# ESP_Home_Automation.net
KiCad netlist of a schematic drawn in EasyEDA
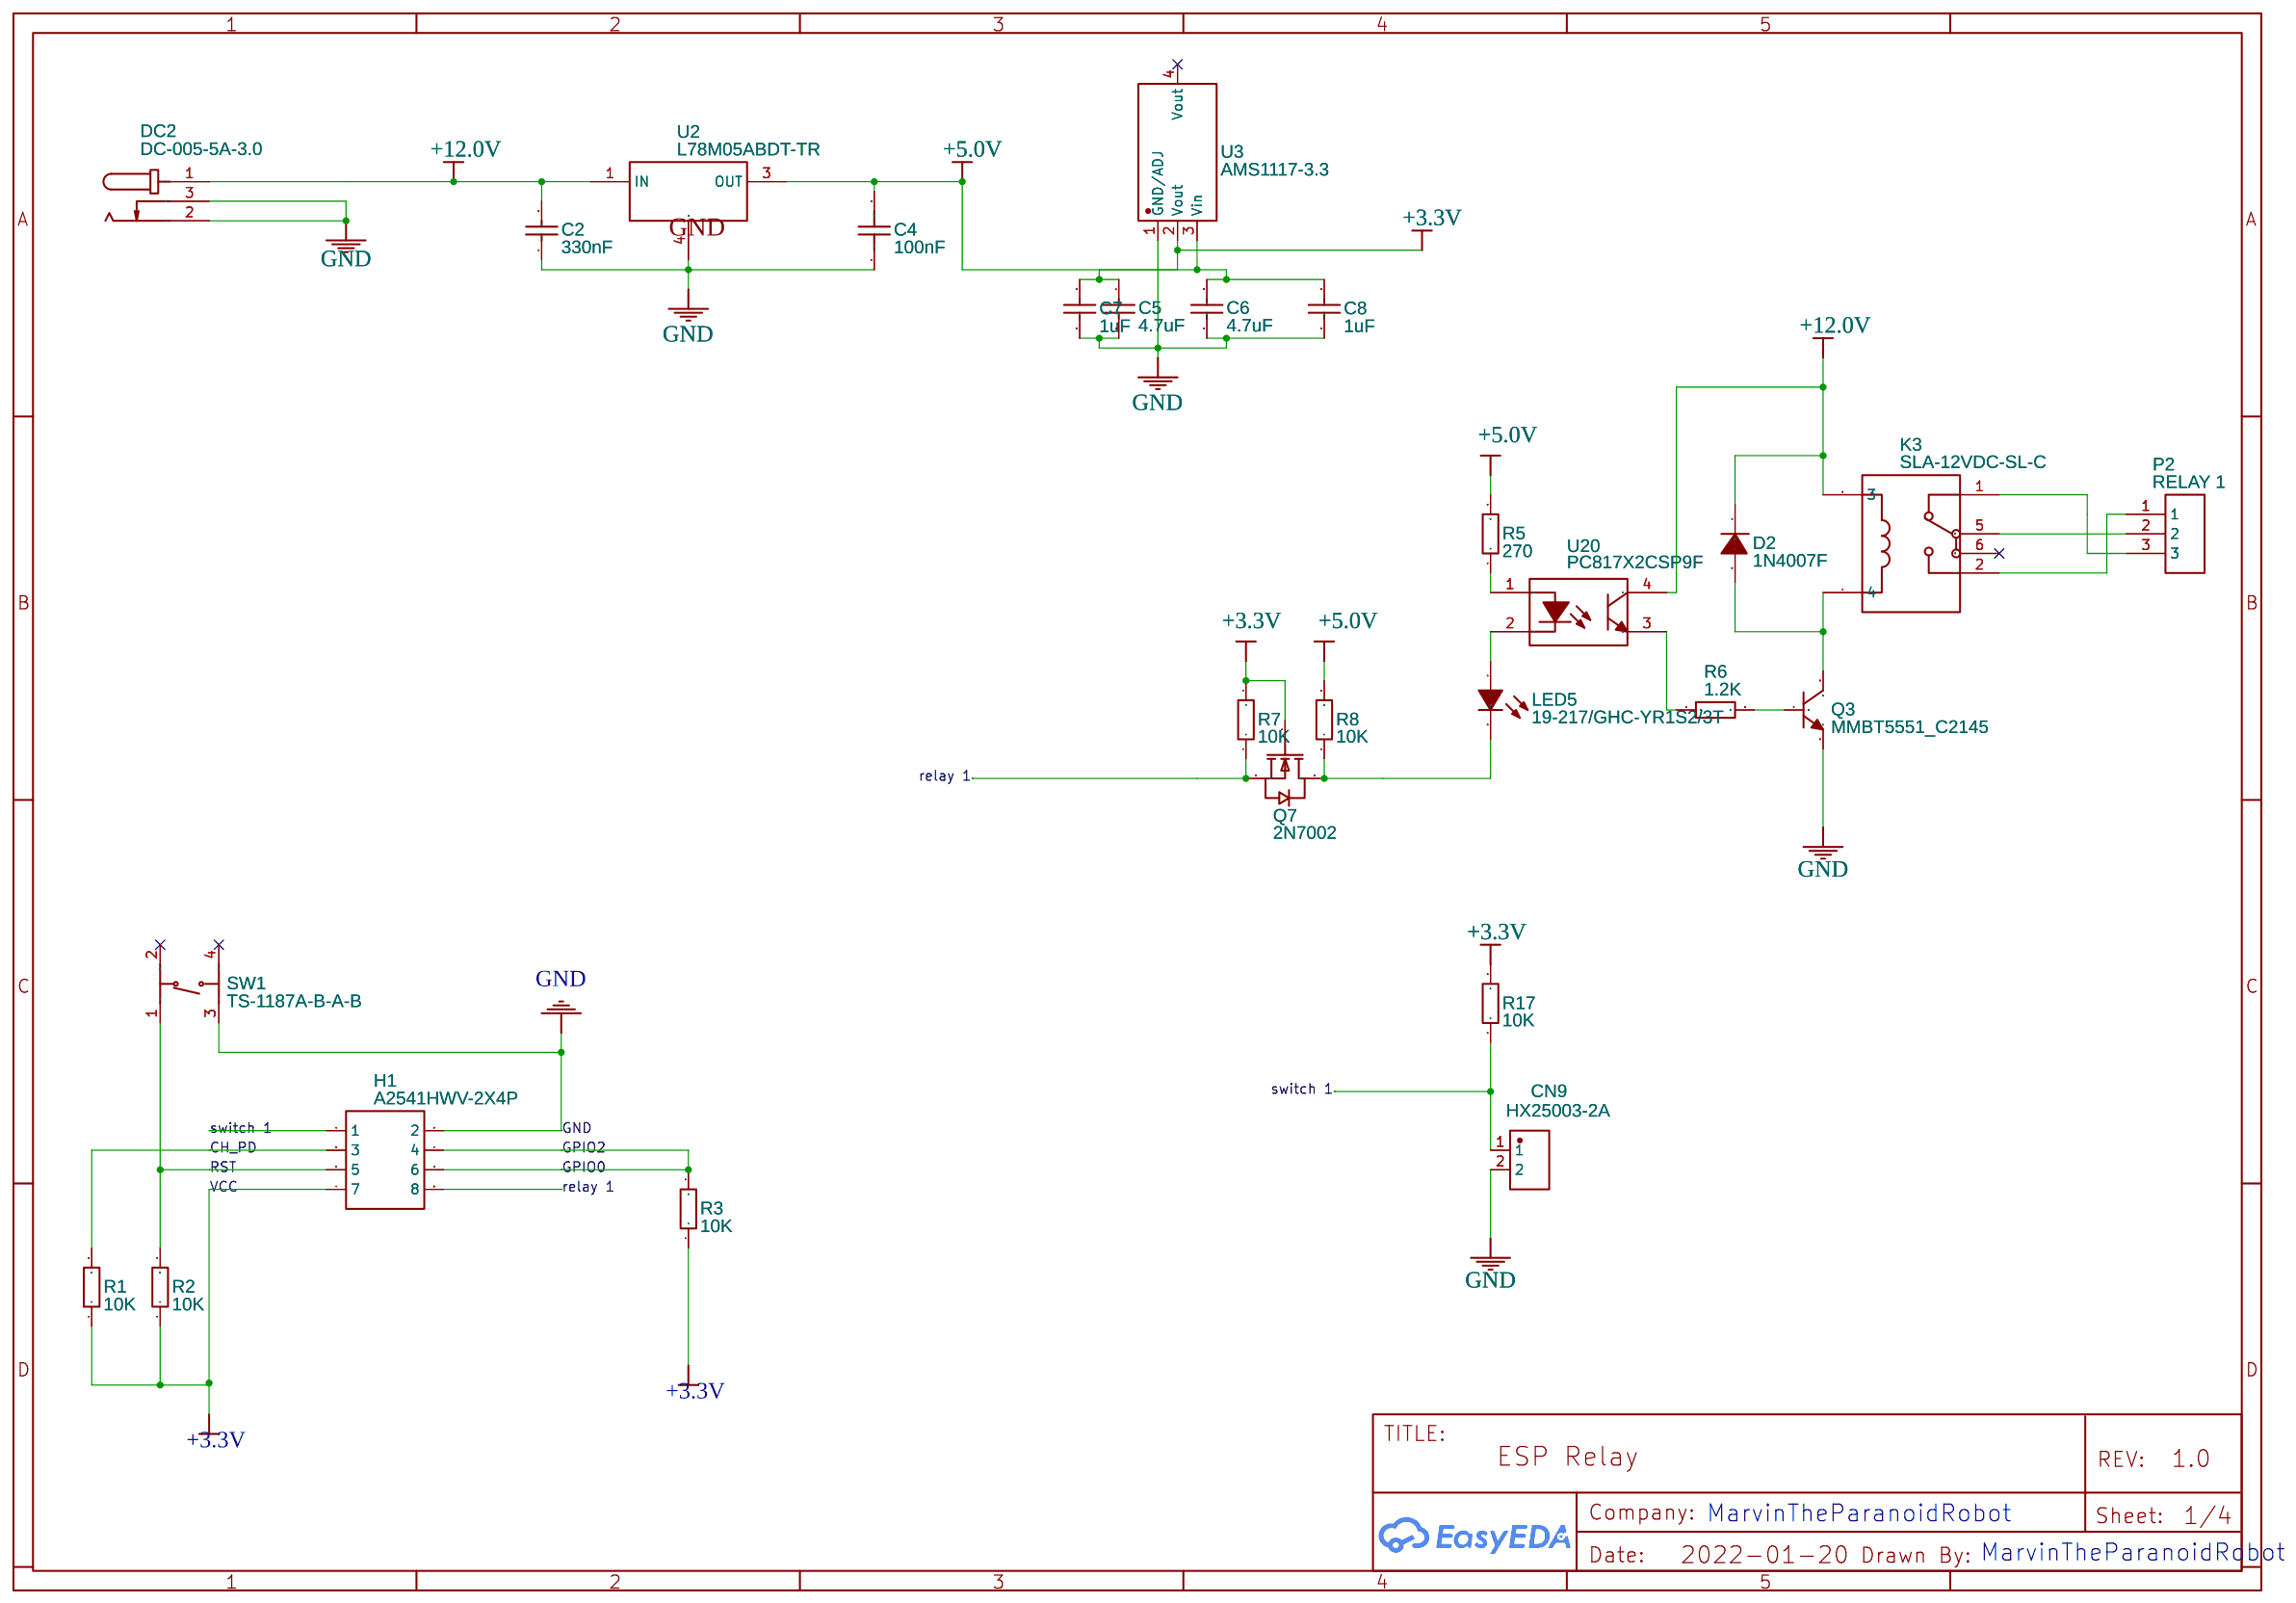
[diagram p0: Sheet_1]
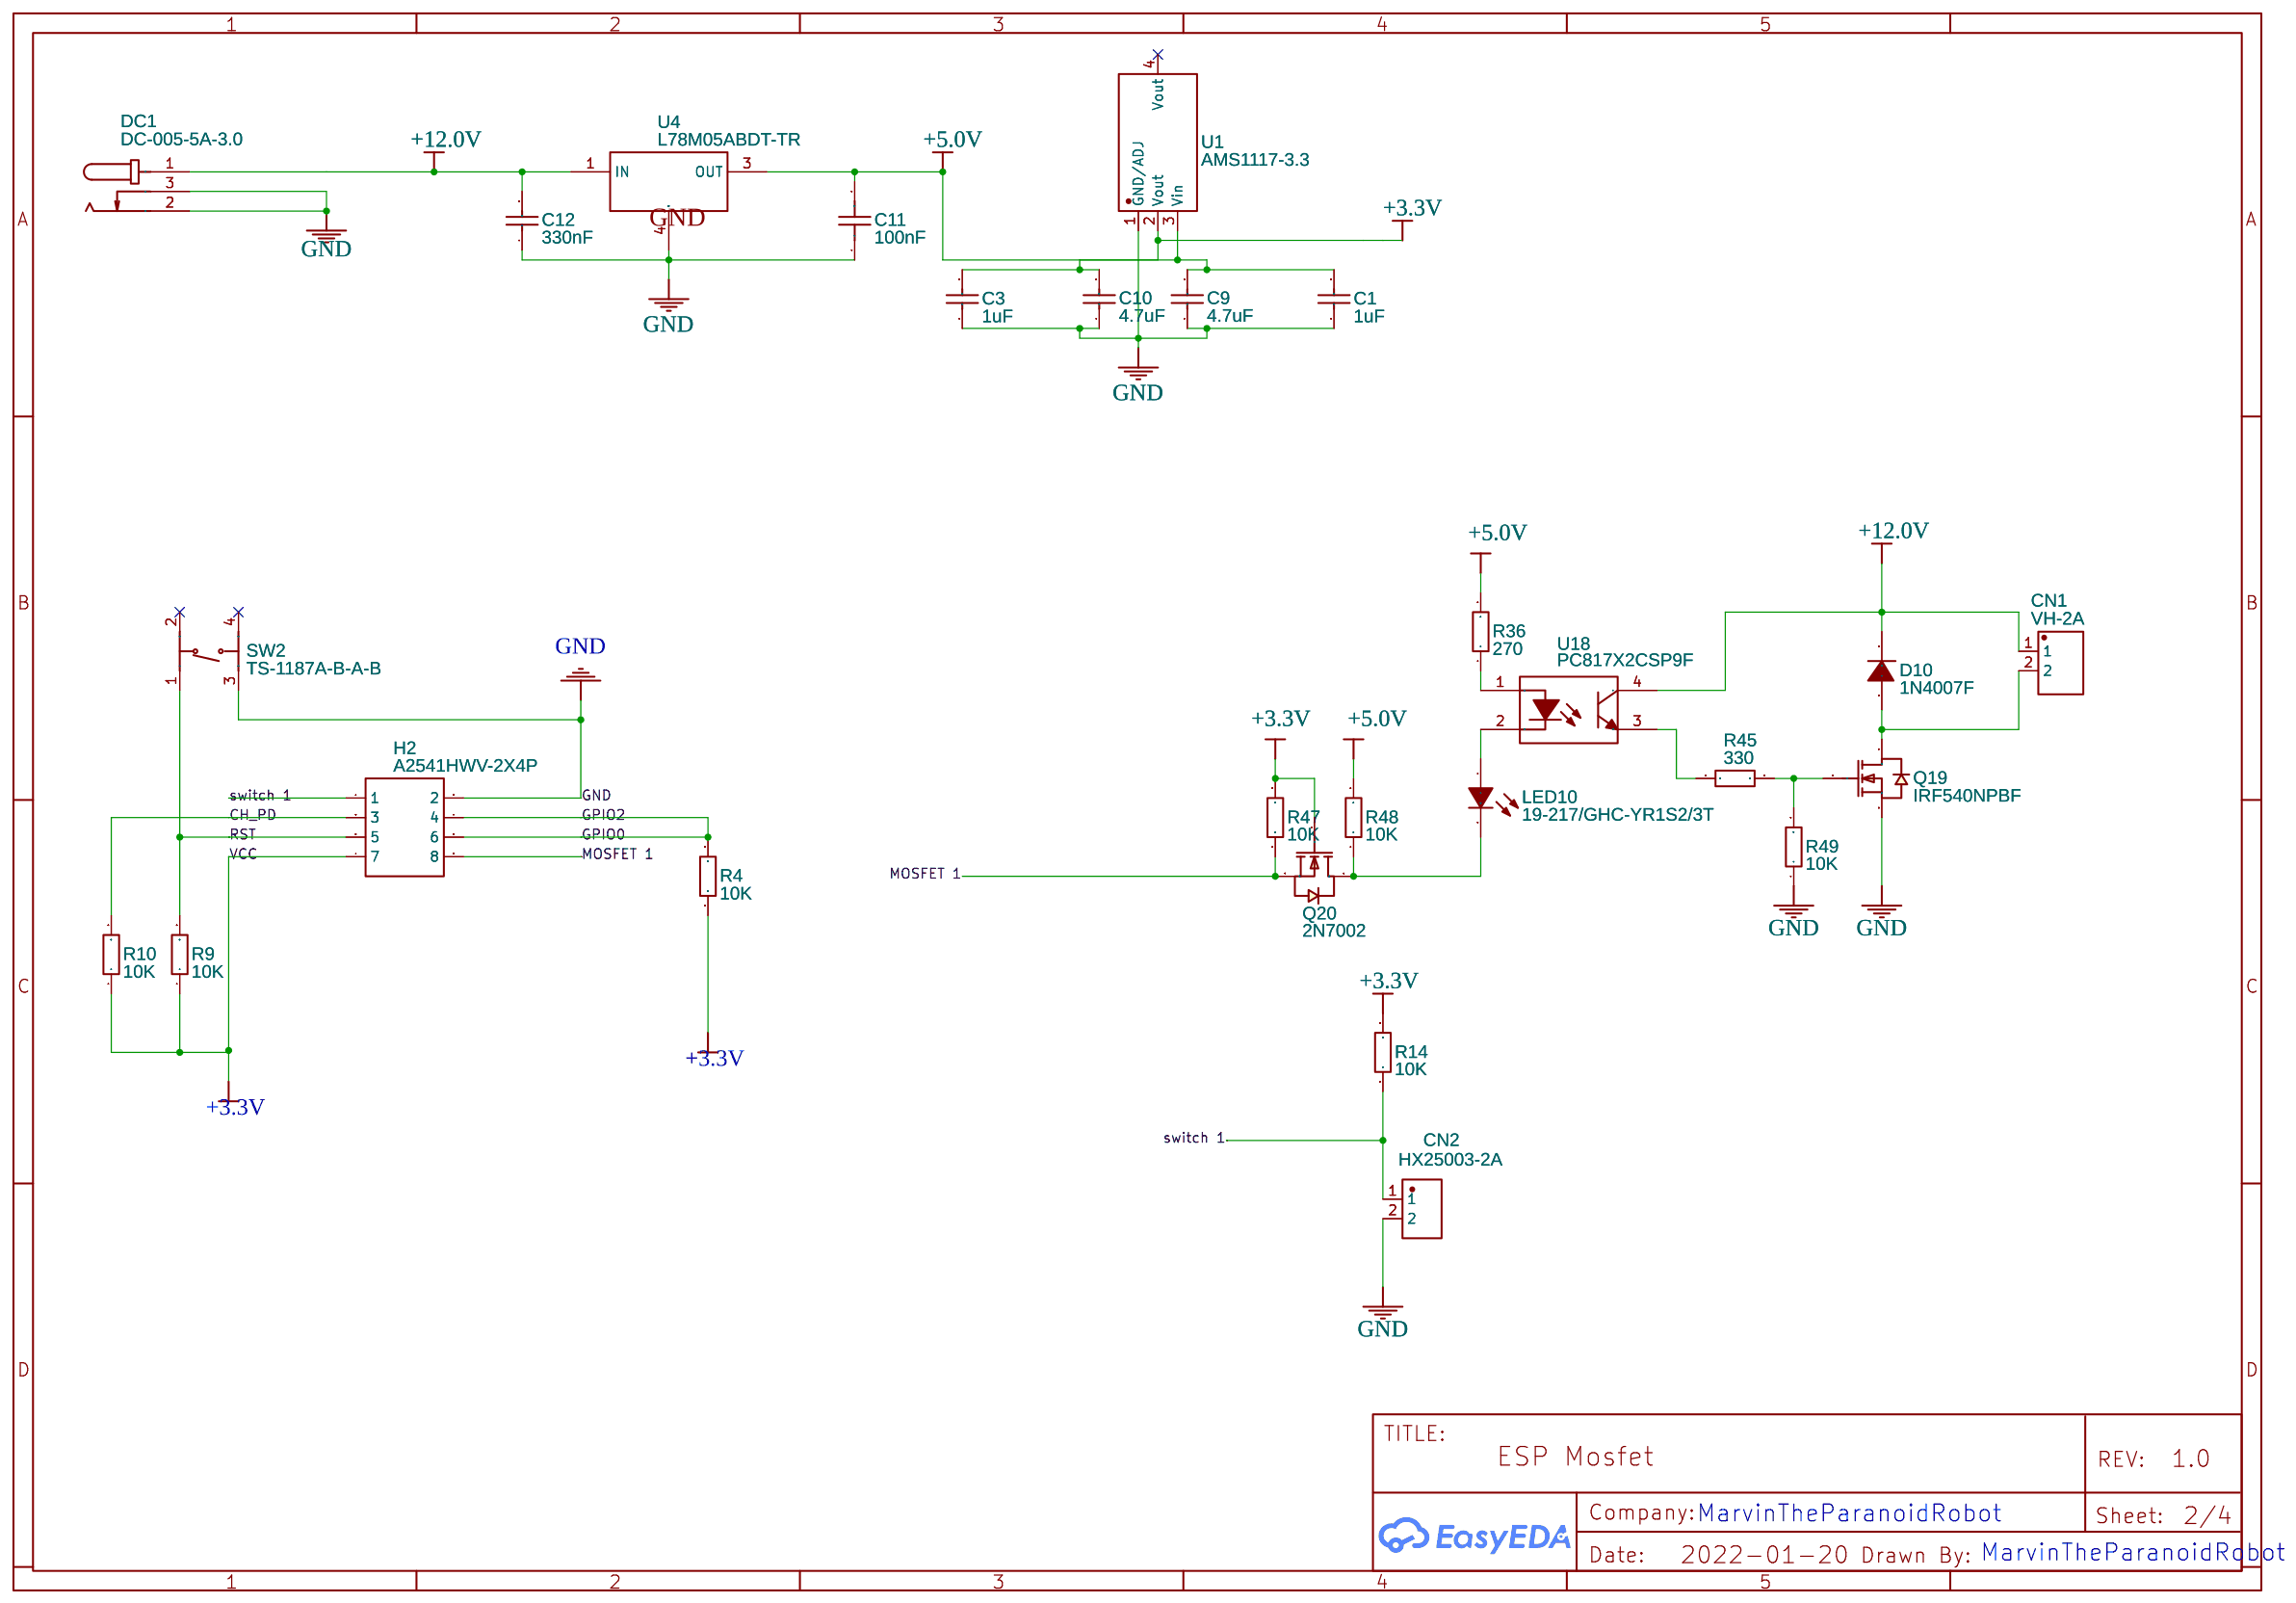
[diagram p1: Sheet_2]
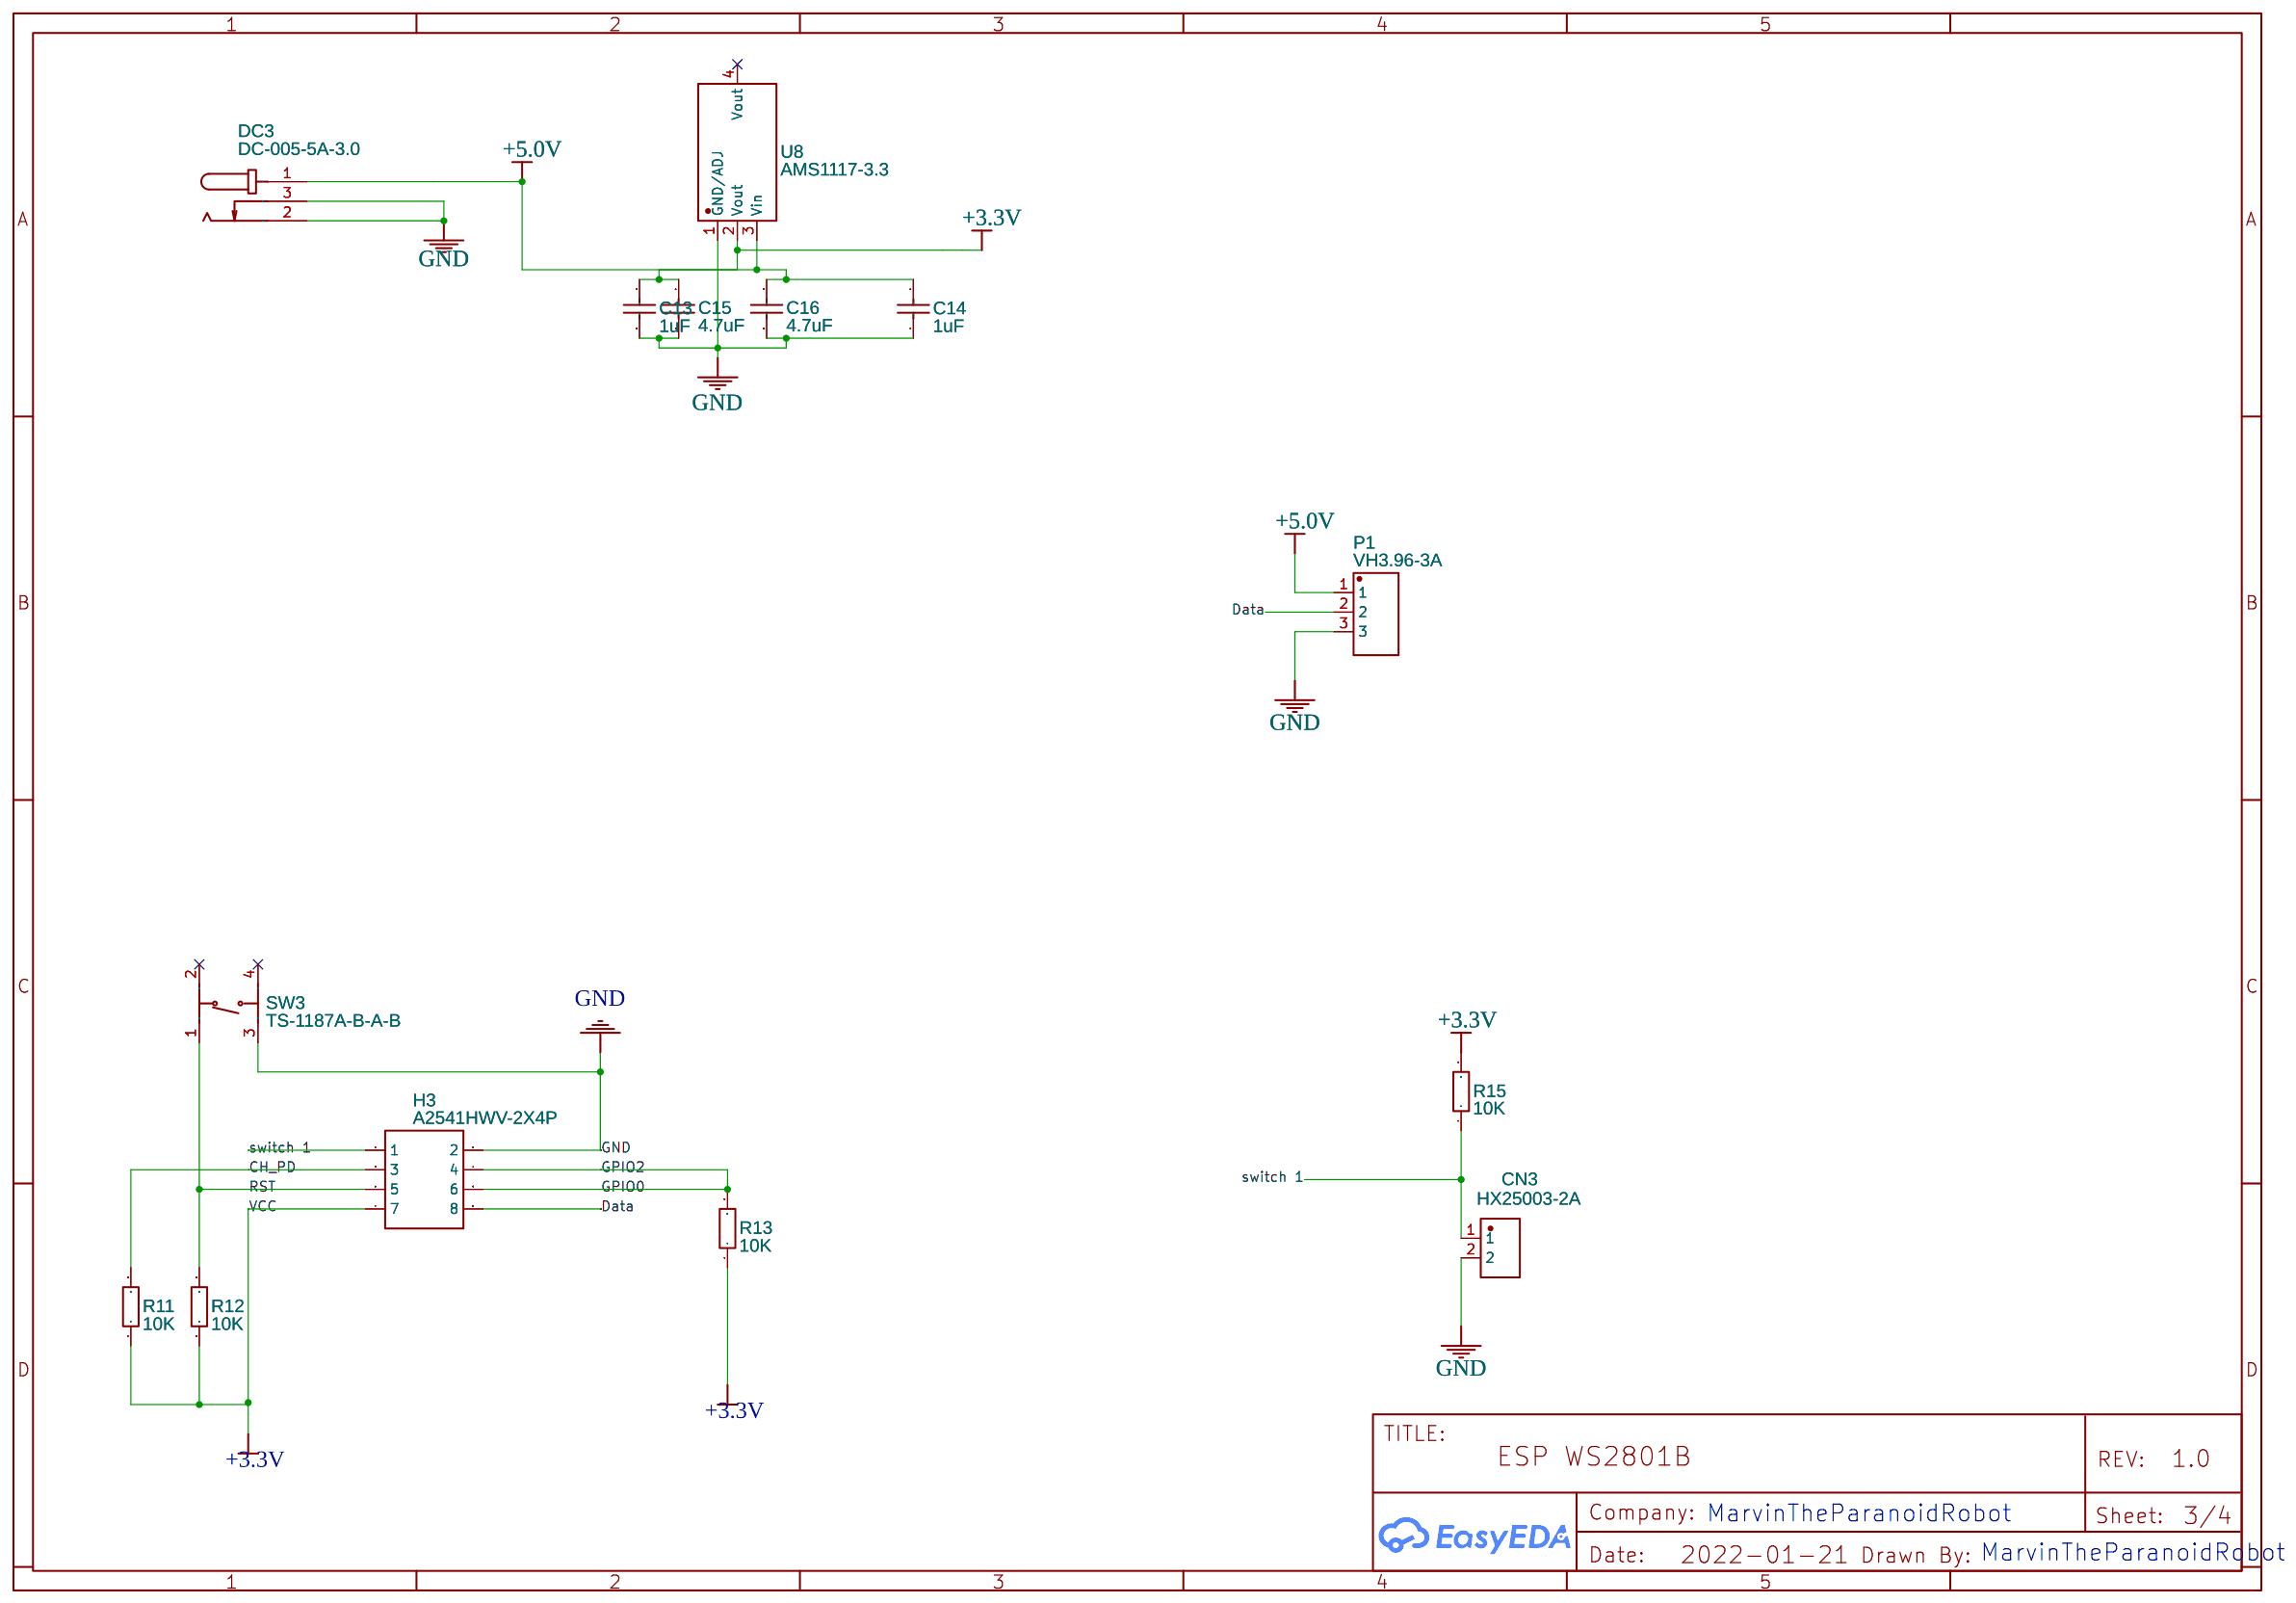
[diagram p2: Sheet_3]
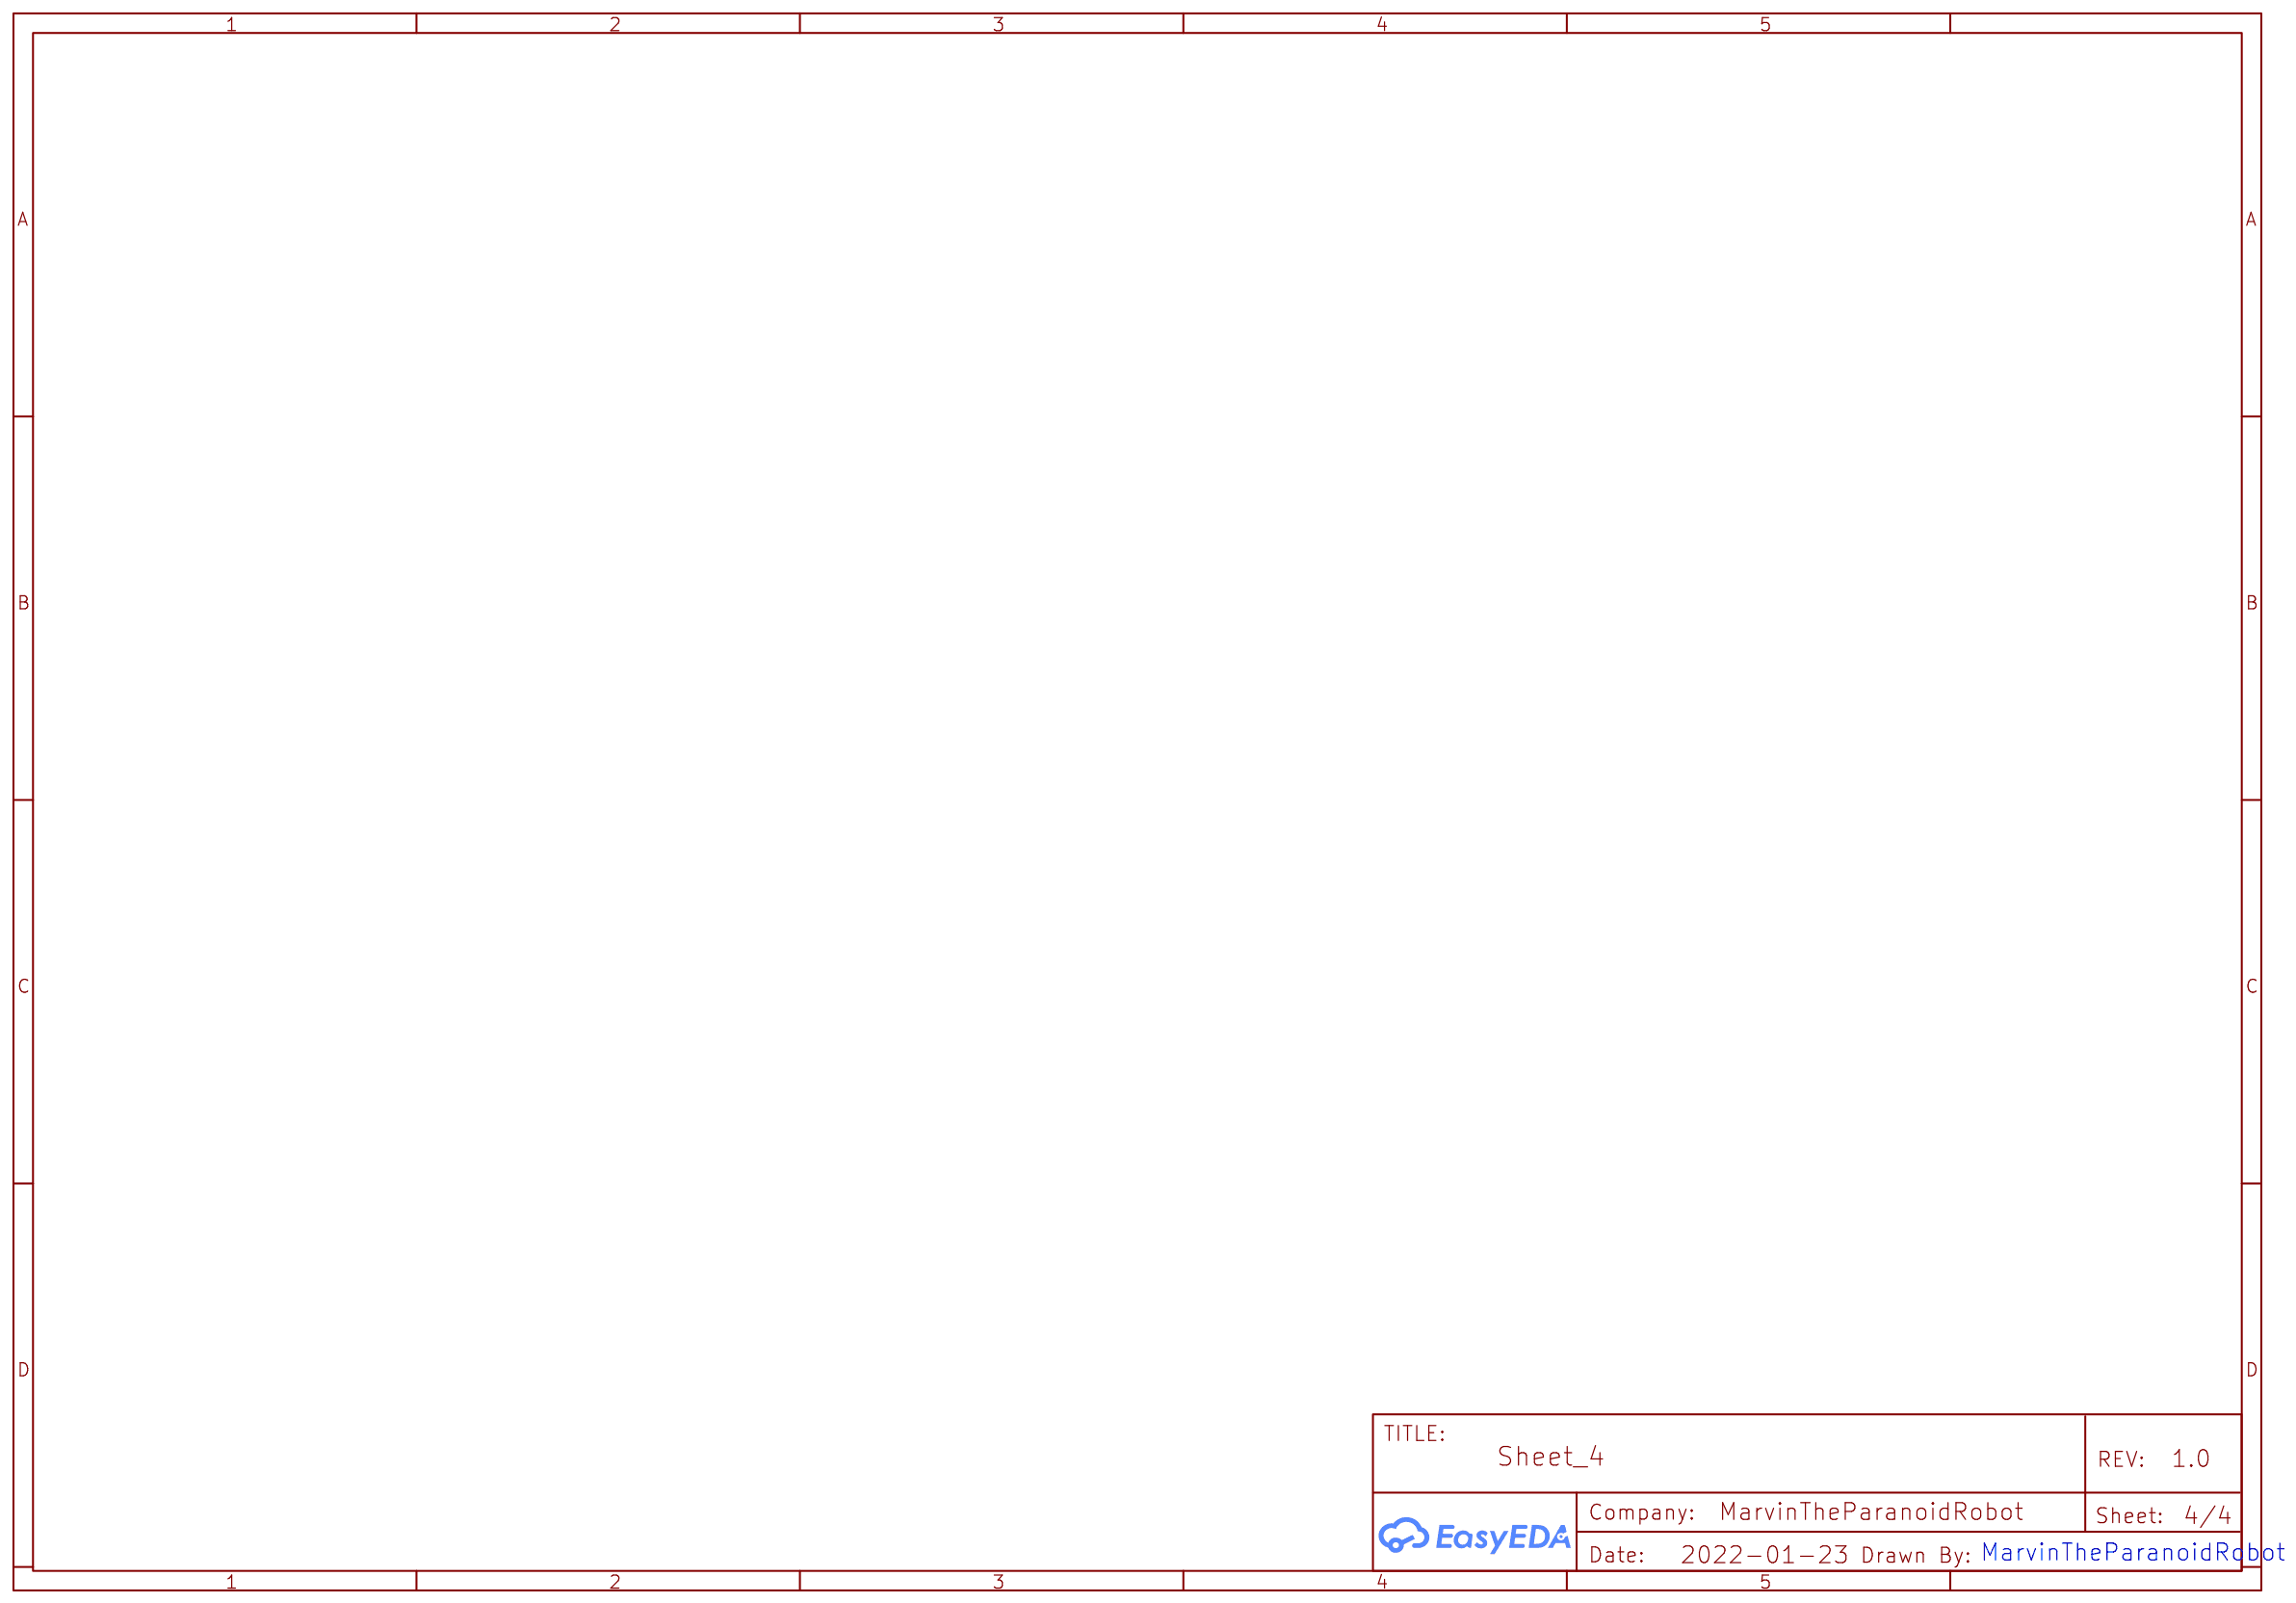
[diagram p3: Sheet_4]

(export (version "E")
  (design (tool "Eeschema 10.0.6"))
  (components
    (comp (ref "C2")
      (value "330nF")
      (fields
        (field (name "BOM_Manufacturer Part") "0805B334K500NT")
        (field (name "BOM_Supplier Part") "C1740")
      )
      (libsource (lib "") (part "0805B334K500NT"))
    )
    (comp (ref "C4")
      (value "100nF")
      (fields
        (field (name "BOM_Manufacturer Part") "CC0603KRX7R9BB104")
        (field (name "BOM_Supplier Part") "C14663")
      )
      (libsource (lib "") (part "CC0603KRX7R9BB104"))
    )
    (comp (ref "C5")
      (value "4.7uF")
      (fields
        (field (name "BOM_Manufacturer Part") "1206B475K500NT")
        (field (name "BOM_Supplier Part") "C29823")
      )
      (libsource (lib "") (part "1206B475K500NT"))
    )
    (comp (ref "C6")
      (value "4.7uF")
      (fields
        (field (name "BOM_Manufacturer Part") "1206B475K500NT")
        (field (name "BOM_Supplier Part") "C29823")
      )
      (libsource (lib "") (part "1206B475K500NT"))
    )
    (comp (ref "C7")
      (value "1uF")
      (fields
        (field (name "BOM_Manufacturer Part") "CL10A105KB8NNNC")
        (field (name "BOM_Supplier Part") "C15849")
      )
      (libsource (lib "") (part "CL10A105KB8NNNC"))
    )
    (comp (ref "C8")
      (value "1uF")
      (fields
        (field (name "BOM_Manufacturer Part") "CL10A105KB8NNNC")
        (field (name "BOM_Supplier Part") "C15849")
      )
      (libsource (lib "") (part "CL10A105KB8NNNC"))
    )
    (comp (ref "CN9")
      (value "HX25003-2A")
      (fields (field (name "BOM_Supplier Part") "C442299"))
      (libsource (lib "") (part "HX25003-2A"))
    )
    (comp (ref "D2")
      (value "1N4007F")
      (fields (field (name "BOM_Supplier Part") "C110856"))
      (libsource (lib "") (part "1N4007F"))
    )
    (comp (ref "DC2")
      (value "DC-005-5A-3.0")
      (fields (field (name "BOM_Supplier Part") "C388625"))
      (libsource (lib "") (part "DC-005-5A-3.0"))
    )
    (comp (ref "H1")
      (value "A2541HWV-2X4P")
      (fields
        (field (name "BOM_Manufacturer Part") "A2541HWV-2x4P")
        (field (name "BOM_Supplier Part") "C239344")
      )
      (libsource (lib "") (part "A2541HWV-2X4P"))
    )
    (comp (ref "K3")
      (value "SLA-12VDC-SL-C")
      (fields (field (name "BOM_Supplier Part") "C125736"))
      (libsource (lib "") (part "SLA-12VDC-SL-C"))
    )
    (comp (ref "LED5")
      (value "19-217/GHC-YR1S2/3T")
      (fields (field (name "BOM_Supplier Part") "C72043"))
      (libsource (lib "") (part "19-217/GHC-YR1S2/3T"))
    )
    (comp (ref "P2")
      (value "RELAY 1")
      (fields
        (field (name "BOM_Manufacturer Part") "WJ128V-5.0-3P")
        (field (name "BOM_Supplier Part") "C8270")
      )
      (libsource (lib "") (part "WJ128V-5.0-3P"))
    )
    (comp (ref "Q3")
      (value "MMBT5551_C2145")
      (fields (field (name "BOM_Manufacturer Part") "MMBT5551") (field (name "BOM_Supplier Part") "C2145"))
      (libsource (lib "") (part "MMBT5551_C2145"))
    )
    (comp (ref "Q7")
      (value "2N7002")
      (fields (field (name "BOM_Supplier Part") "C8545"))
      (libsource (lib "") (part "2N7002"))
    )
    (comp (ref "R1")
      (value "10K")
      (fields
        (field (name "BOM_Manufacturer Part") "1206W4F1002T5E")
        (field (name "BOM_Supplier Part") "C17902")
      )
      (libsource (lib "") (part "1206W4F1002T5E"))
    )
    (comp (ref "R2")
      (value "10K")
      (fields
        (field (name "BOM_Manufacturer Part") "1206W4F1002T5E")
        (field (name "BOM_Supplier Part") "C17902")
      )
      (libsource (lib "") (part "1206W4F1002T5E"))
    )
    (comp (ref "R3")
      (value "10K")
      (fields
        (field (name "BOM_Manufacturer Part") "1206W4F1002T5E")
        (field (name "BOM_Supplier Part") "C17902")
      )
      (libsource (lib "") (part "1206W4F1002T5E"))
    )
    (comp (ref "R5")
      (value "270")
      (fields
        (field (name "BOM_Manufacturer Part") "0603WAF2700T5E")
        (field (name "BOM_Supplier Part") "C22966")
      )
      (libsource (lib "") (part "0603WAF2700T5E"))
    )
    (comp (ref "R6")
      (value "1.2K")
      (fields
        (field (name "BOM_Manufacturer Part") "0805W8F1201T5E")
        (field (name "BOM_Supplier Part") "C17379")
      )
      (libsource (lib "") (part "0805W8F1201T5E"))
    )
    (comp (ref "R7")
      (value "10K")
      (fields
        (field (name "BOM_Manufacturer Part") "1206W4F1002T5E")
        (field (name "BOM_Supplier Part") "C17902")
      )
      (libsource (lib "") (part "1206W4F1002T5E"))
    )
    (comp (ref "R8")
      (value "10K")
      (fields
        (field (name "BOM_Manufacturer Part") "1206W4F1002T5E")
        (field (name "BOM_Supplier Part") "C17902")
      )
      (libsource (lib "") (part "1206W4F1002T5E"))
    )
    (comp (ref "R17")
      (value "10K")
      (fields
        (field (name "BOM_Manufacturer Part") "1206W4F1002T5E")
        (field (name "BOM_Supplier Part") "C17902")
      )
      (libsource (lib "") (part "1206W4F1002T5E"))
    )
    (comp (ref "SW1")
      (value "TS-1187A-B-A-B")
      (fields (field (name "BOM_Supplier Part") "C318884"))
      (libsource (lib "") (part "TS-1187A-B-A-B"))
    )
    (comp (ref "U2")
      (value "L78M05ABDT-TR")
      (fields (field (name "BOM_Supplier Part") "C58069"))
      (libsource (lib "") (part "L78M05ABDT-TR"))
    )
    (comp (ref "U3")
      (value "AMS1117-3.3")
      (fields (field (name "BOM_Supplier Part") "C6186"))
      (libsource (lib "") (part "AMS1117-3.3"))
    )
    (comp (ref "U20")
      (value "PC817X2CSP9F")
      (fields (field (name "BOM_Supplier Part") "C66405"))
      (libsource (lib "") (part "PC817X2CSP9F"))
    )
    (comp (ref "C1")
      (value "1uF")
      (fields
        (field (name "BOM_Manufacturer Part") "CL10A105KB8NNNC")
        (field (name "BOM_Supplier Part") "C15849")
      )
      (libsource (lib "") (part "CL10A105KB8NNNC"))
    )
    (comp (ref "C3")
      (value "1uF")
      (fields
        (field (name "BOM_Manufacturer Part") "CL10A105KB8NNNC")
        (field (name "BOM_Supplier Part") "C15849")
      )
      (libsource (lib "") (part "CL10A105KB8NNNC"))
    )
    (comp (ref "C9")
      (value "4.7uF")
      (fields
        (field (name "BOM_Manufacturer Part") "1206B475K500NT")
        (field (name "BOM_Supplier Part") "C29823")
      )
      (libsource (lib "") (part "1206B475K500NT"))
    )
    (comp (ref "C10")
      (value "4.7uF")
      (fields
        (field (name "BOM_Manufacturer Part") "1206B475K500NT")
        (field (name "BOM_Supplier Part") "C29823")
      )
      (libsource (lib "") (part "1206B475K500NT"))
    )
    (comp (ref "C11")
      (value "100nF")
      (fields
        (field (name "BOM_Manufacturer Part") "CC0603KRX7R9BB104")
        (field (name "BOM_Supplier Part") "C14663")
      )
      (libsource (lib "") (part "CC0603KRX7R9BB104"))
    )
    (comp (ref "C12")
      (value "330nF")
      (fields
        (field (name "BOM_Manufacturer Part") "0805B334K500NT")
        (field (name "BOM_Supplier Part") "C1740")
      )
      (libsource (lib "") (part "0805B334K500NT"))
    )
    (comp (ref "CN1")
      (value "VH-2A")
      (fields (field (name "BOM_Supplier Part") "C16728"))
      (libsource (lib "") (part "VH-2A"))
    )
    (comp (ref "CN2")
      (value "HX25003-2A")
      (fields (field (name "BOM_Supplier Part") "C442299"))
      (libsource (lib "") (part "HX25003-2A"))
    )
    (comp (ref "D10")
      (value "1N4007F")
      (fields (field (name "BOM_Supplier Part") "C110856"))
      (libsource (lib "") (part "1N4007F"))
    )
    (comp (ref "DC1")
      (value "DC-005-5A-3.0")
      (fields (field (name "BOM_Supplier Part") "C388625"))
      (libsource (lib "") (part "DC-005-5A-3.0"))
    )
    (comp (ref "H2")
      (value "A2541HWV-2X4P")
      (fields
        (field (name "BOM_Manufacturer Part") "A2541HWV-2x4P")
        (field (name "BOM_Supplier Part") "C239344")
      )
      (libsource (lib "") (part "A2541HWV-2X4P"))
    )
    (comp (ref "LED10")
      (value "19-217/GHC-YR1S2/3T")
      (fields (field (name "BOM_Supplier Part") "C72043"))
      (libsource (lib "") (part "19-217/GHC-YR1S2/3T"))
    )
    (comp (ref "Q19")
      (value "IRF540NPBF")
      (fields (field (name "BOM_Supplier Part") "C2566"))
      (libsource (lib "") (part "IRF540NPBF"))
    )
    (comp (ref "Q20")
      (value "2N7002")
      (fields (field (name "BOM_Supplier Part") "C8545"))
      (libsource (lib "") (part "2N7002"))
    )
    (comp (ref "R4")
      (value "10K")
      (fields
        (field (name "BOM_Manufacturer Part") "1206W4F1002T5E")
        (field (name "BOM_Supplier Part") "C17902")
      )
      (libsource (lib "") (part "1206W4F1002T5E"))
    )
    (comp (ref "R9")
      (value "10K")
      (fields
        (field (name "BOM_Manufacturer Part") "1206W4F1002T5E")
        (field (name "BOM_Supplier Part") "C17902")
      )
      (libsource (lib "") (part "1206W4F1002T5E"))
    )
    (comp (ref "R10")
      (value "10K")
      (fields
        (field (name "BOM_Manufacturer Part") "1206W4F1002T5E")
        (field (name "BOM_Supplier Part") "C17902")
      )
      (libsource (lib "") (part "1206W4F1002T5E"))
    )
    (comp (ref "R14")
      (value "10K")
      (fields
        (field (name "BOM_Manufacturer Part") "1206W4F1002T5E")
        (field (name "BOM_Supplier Part") "C17902")
      )
      (libsource (lib "") (part "1206W4F1002T5E"))
    )
    (comp (ref "R36")
      (value "270")
      (fields
        (field (name "BOM_Manufacturer Part") "0603WAF2700T5E")
        (field (name "BOM_Supplier Part") "C22966")
      )
      (libsource (lib "") (part "0603WAF2700T5E"))
    )
    (comp (ref "R45")
      (value "330")
      (fields
        (field (name "BOM_Manufacturer Part") "0805W8F3300T5E")
        (field (name "BOM_Supplier Part") "C17630")
      )
      (libsource (lib "") (part "0805W8F3300T5E"))
    )
    (comp (ref "R47")
      (value "10K")
      (fields
        (field (name "BOM_Manufacturer Part") "1206W4F1002T5E")
        (field (name "BOM_Supplier Part") "C17902")
      )
      (libsource (lib "") (part "1206W4F1002T5E"))
    )
    (comp (ref "R48")
      (value "10K")
      (fields
        (field (name "BOM_Manufacturer Part") "1206W4F1002T5E")
        (field (name "BOM_Supplier Part") "C17902")
      )
      (libsource (lib "") (part "1206W4F1002T5E"))
    )
    (comp (ref "R49")
      (value "10K")
      (fields
        (field (name "BOM_Manufacturer Part") "1206W4F1002T5E")
        (field (name "BOM_Supplier Part") "C17902")
      )
      (libsource (lib "") (part "1206W4F1002T5E"))
    )
    (comp (ref "SW2")
      (value "TS-1187A-B-A-B")
      (fields (field (name "BOM_Supplier Part") "C318884"))
      (libsource (lib "") (part "TS-1187A-B-A-B"))
    )
    (comp (ref "U1")
      (value "AMS1117-3.3")
      (fields (field (name "BOM_Supplier Part") "C6186"))
      (libsource (lib "") (part "AMS1117-3.3"))
    )
    (comp (ref "U4")
      (value "L78M05ABDT-TR")
      (fields (field (name "BOM_Supplier Part") "C58069"))
      (libsource (lib "") (part "L78M05ABDT-TR"))
    )
    (comp (ref "U18")
      (value "PC817X2CSP9F")
      (fields (field (name "BOM_Supplier Part") "C66405"))
      (libsource (lib "") (part "PC817X2CSP9F"))
    )
    (comp (ref "C13")
      (value "1uF")
      (fields
        (field (name "BOM_Manufacturer Part") "CL10A105KB8NNNC")
        (field (name "BOM_Supplier Part") "C15849")
      )
      (libsource (lib "") (part "CL10A105KB8NNNC"))
    )
    (comp (ref "C14")
      (value "1uF")
      (fields
        (field (name "BOM_Manufacturer Part") "CL10A105KB8NNNC")
        (field (name "BOM_Supplier Part") "C15849")
      )
      (libsource (lib "") (part "CL10A105KB8NNNC"))
    )
    (comp (ref "C15")
      (value "4.7uF")
      (fields
        (field (name "BOM_Manufacturer Part") "1206B475K500NT")
        (field (name "BOM_Supplier Part") "C29823")
      )
      (libsource (lib "") (part "1206B475K500NT"))
    )
    (comp (ref "C16")
      (value "4.7uF")
      (fields
        (field (name "BOM_Manufacturer Part") "1206B475K500NT")
        (field (name "BOM_Supplier Part") "C29823")
      )
      (libsource (lib "") (part "1206B475K500NT"))
    )
    (comp (ref "CN3")
      (value "HX25003-2A")
      (fields (field (name "BOM_Supplier Part") "C442299"))
      (libsource (lib "") (part "HX25003-2A"))
    )
    (comp (ref "DC3")
      (value "DC-005-5A-3.0")
      (fields (field (name "BOM_Supplier Part") "C388625"))
      (libsource (lib "") (part "DC-005-5A-3.0"))
    )
    (comp (ref "H3")
      (value "A2541HWV-2X4P")
      (fields
        (field (name "BOM_Manufacturer Part") "A2541HWV-2x4P")
        (field (name "BOM_Supplier Part") "C239344")
      )
      (libsource (lib "") (part "A2541HWV-2X4P"))
    )
    (comp (ref "P1")
      (value "VH3.96-3A")
      (fields (field (name "BOM_Supplier Part") "C20547"))
      (libsource (lib "") (part "VH3.96-3A"))
    )
    (comp (ref "R11")
      (value "10K")
      (fields
        (field (name "BOM_Manufacturer Part") "1206W4F1002T5E")
        (field (name "BOM_Supplier Part") "C17902")
      )
      (libsource (lib "") (part "1206W4F1002T5E"))
    )
    (comp (ref "R12")
      (value "10K")
      (fields
        (field (name "BOM_Manufacturer Part") "1206W4F1002T5E")
        (field (name "BOM_Supplier Part") "C17902")
      )
      (libsource (lib "") (part "1206W4F1002T5E"))
    )
    (comp (ref "R13")
      (value "10K")
      (fields
        (field (name "BOM_Manufacturer Part") "1206W4F1002T5E")
        (field (name "BOM_Supplier Part") "C17902")
      )
      (libsource (lib "") (part "1206W4F1002T5E"))
    )
    (comp (ref "R15")
      (value "10K")
      (fields
        (field (name "BOM_Manufacturer Part") "1206W4F1002T5E")
        (field (name "BOM_Supplier Part") "C17902")
      )
      (libsource (lib "") (part "1206W4F1002T5E"))
    )
    (comp (ref "SW3")
      (value "TS-1187A-B-A-B")
      (fields (field (name "BOM_Supplier Part") "C318884"))
      (libsource (lib "") (part "TS-1187A-B-A-B"))
    )
    (comp (ref "U8")
      (value "AMS1117-3.3")
      (fields (field (name "BOM_Supplier Part") "C6186"))
      (libsource (lib "") (part "AMS1117-3.3"))
    )
  )
  (nets
    (net (code "1") (name "+5.0V") (class "Default")
      (node (ref "C1") (pin "2") (pinfunction "2_2") (pintype "input"))
      (node (ref "C11") (pin "2") (pinfunction "2_2") (pintype "unspecified"))
      (node (ref "C14") (pin "2") (pinfunction "2_2") (pintype "input"))
      (node (ref "C16") (pin "2") (pinfunction "2_2") (pintype "input"))
      (node (ref "C4") (pin "2") (pinfunction "2_2") (pintype "unspecified"))
      (node (ref "C6") (pin "2") (pinfunction "2_2") (pintype "input"))
      (node (ref "C8") (pin "2") (pinfunction "2_2") (pintype "input"))
      (node (ref "C9") (pin "2") (pinfunction "2_2") (pintype "input"))
      (node (ref "DC3") (pin "1") (pinfunction "1_1") (pintype "unspecified"))
      (node (ref "P1") (pin "1") (pinfunction "1_1") (pintype "unspecified"))
      (node (ref "R36") (pin "2") (pinfunction "2_2") (pintype "input"))
      (node (ref "R48") (pin "2") (pinfunction "2_2") (pintype "input"))
      (node (ref "R5") (pin "2") (pinfunction "2_2") (pintype "input"))
      (node (ref "R8") (pin "2") (pinfunction "2_2") (pintype "input"))
      (node (ref "U1") (pin "3") (pinfunction "Vin_3") (pintype "unspecified"))
      (node (ref "U2") (pin "3") (pinfunction "OUT_3") (pintype "passive"))
      (node (ref "U3") (pin "3") (pinfunction "Vin_3") (pintype "unspecified"))
      (node (ref "U4") (pin "3") (pinfunction "OUT_3") (pintype "passive"))
      (node (ref "U8") (pin "3") (pinfunction "Vin_3") (pintype "unspecified"))
    )
    (net (code "2") (name "+12.0V") (class "Default")
      (node (ref "C12") (pin "2") (pinfunction "2_2") (pintype "input"))
      (node (ref "C2") (pin "2") (pinfunction "2_2") (pintype "input"))
      (node (ref "CN1") (pin "1") (pinfunction "1_1") (pintype "unspecified"))
      (node (ref "D10") (pin "1") (pinfunction "C_1") (pintype "unspecified"))
      (node (ref "D2") (pin "1") (pinfunction "C_1") (pintype "unspecified"))
      (node (ref "DC1") (pin "1") (pinfunction "1_1") (pintype "unspecified"))
      (node (ref "DC2") (pin "1") (pinfunction "1_1") (pintype "unspecified"))
      (node (ref "K3") (pin "3") (pinfunction "3_3") (pintype "unspecified"))
      (node (ref "U18") (pin "4") (pinfunction "4_4") (pintype "unspecified"))
      (node (ref "U2") (pin "1") (pinfunction "IN_1") (pintype "passive"))
      (node (ref "U20") (pin "4") (pinfunction "4_4") (pintype "unspecified"))
      (node (ref "U4") (pin "1") (pinfunction "IN_1") (pintype "passive"))
    )
    (net (code "3") (name "CH_PD") (class "Default")
      (node (ref "H1") (pin "3") (pinfunction "3_3") (pintype "input"))
      (node (ref "H2") (pin "3") (pinfunction "3_3") (pintype "input"))
      (node (ref "H3") (pin "3") (pinfunction "3_3") (pintype "input"))
      (node (ref "R1") (pin "2") (pinfunction "2_2") (pintype "input"))
      (node (ref "R10") (pin "2") (pinfunction "2_2") (pintype "input"))
      (node (ref "R11") (pin "2") (pinfunction "2_2") (pintype "input"))
    )
    (net (code "4") (name "Data") (class "Default")
      (node (ref "H3") (pin "8") (pinfunction "8_8") (pintype "input"))
      (node (ref "P1") (pin "2") (pinfunction "2_2") (pintype "unspecified"))
    )
    (net (code "5") (name "GND") (class "Default")
      (node (ref "C1") (pin "1") (pinfunction "1_1") (pintype "input"))
      (node (ref "C10") (pin "1") (pinfunction "1_1") (pintype "input"))
      (node (ref "C11") (pin "1") (pinfunction "1_1") (pintype "unspecified"))
      (node (ref "C12") (pin "1") (pinfunction "1_1") (pintype "input"))
      (node (ref "C13") (pin "1") (pinfunction "1_1") (pintype "input"))
      (node (ref "C14") (pin "1") (pinfunction "1_1") (pintype "input"))
      (node (ref "C15") (pin "1") (pinfunction "1_1") (pintype "input"))
      (node (ref "C16") (pin "1") (pinfunction "1_1") (pintype "input"))
      (node (ref "C2") (pin "1") (pinfunction "1_1") (pintype "input"))
      (node (ref "C3") (pin "1") (pinfunction "1_1") (pintype "input"))
      (node (ref "C4") (pin "1") (pinfunction "1_1") (pintype "unspecified"))
      (node (ref "C5") (pin "1") (pinfunction "1_1") (pintype "input"))
      (node (ref "C6") (pin "1") (pinfunction "1_1") (pintype "input"))
      (node (ref "C7") (pin "1") (pinfunction "1_1") (pintype "input"))
      (node (ref "C8") (pin "1") (pinfunction "1_1") (pintype "input"))
      (node (ref "C9") (pin "1") (pinfunction "1_1") (pintype "input"))
      (node (ref "CN2") (pin "2") (pinfunction "2_2") (pintype "unspecified"))
      (node (ref "CN3") (pin "2") (pinfunction "2_2") (pintype "unspecified"))
      (node (ref "CN9") (pin "2") (pinfunction "2_2") (pintype "unspecified"))
      (node (ref "DC1") (pin "2") (pinfunction "2_2") (pintype "unspecified"))
      (node (ref "DC1") (pin "3") (pinfunction "3_3") (pintype "unspecified"))
      (node (ref "DC2") (pin "2") (pinfunction "2_2") (pintype "unspecified"))
      (node (ref "DC2") (pin "3") (pinfunction "3_3") (pintype "unspecified"))
      (node (ref "DC3") (pin "2") (pinfunction "2_2") (pintype "unspecified"))
      (node (ref "DC3") (pin "3") (pinfunction "3_3") (pintype "unspecified"))
      (node (ref "H1") (pin "2") (pinfunction "2_2") (pintype "input"))
      (node (ref "H2") (pin "2") (pinfunction "2_2") (pintype "input"))
      (node (ref "H3") (pin "2") (pinfunction "2_2") (pintype "input"))
      (node (ref "P1") (pin "3") (pinfunction "3_3") (pintype "unspecified"))
      (node (ref "Q19") (pin "3") (pinfunction "S_3") (pintype "unspecified"))
      (node (ref "Q3") (pin "2") (pinfunction "E_2") (pintype "unspecified"))
      (node (ref "R49") (pin "1") (pinfunction "1_1") (pintype "input"))
      (node (ref "SW1") (pin "3") (pinfunction "C_3") (pintype "unspecified"))
      (node (ref "SW2") (pin "3") (pinfunction "C_3") (pintype "unspecified"))
      (node (ref "SW3") (pin "3") (pinfunction "C_3") (pintype "unspecified"))
      (node (ref "U1") (pin "1") (pinfunction "GND/ADJ_1") (pintype "unspecified"))
      (node (ref "U2") (pin "4") (pinfunction "GND_4") (pintype "passive"))
      (node (ref "U3") (pin "1") (pinfunction "GND/ADJ_1") (pintype "unspecified"))
      (node (ref "U4") (pin "4") (pinfunction "GND_4") (pintype "passive"))
      (node (ref "U8") (pin "1") (pinfunction "GND/ADJ_1") (pintype "unspecified"))
    )
    (net (code "6") (name "GPIO0") (class "Default")
      (node (ref "H1") (pin "4") (pinfunction "4_4") (pintype "input"))
      (node (ref "H1") (pin "6") (pinfunction "6_6") (pintype "input"))
      (node (ref "H2") (pin "4") (pinfunction "4_4") (pintype "input"))
      (node (ref "H2") (pin "6") (pinfunction "6_6") (pintype "input"))
      (node (ref "H3") (pin "4") (pinfunction "4_4") (pintype "input"))
      (node (ref "H3") (pin "6") (pinfunction "6_6") (pintype "input"))
      (node (ref "R13") (pin "2") (pinfunction "2_2") (pintype "input"))
      (node (ref "R3") (pin "2") (pinfunction "2_2") (pintype "input"))
      (node (ref "R4") (pin "2") (pinfunction "2_2") (pintype "input"))
    )
    (net (code "7") (name "MOSFET 1") (class "Default")
      (node (ref "H2") (pin "8") (pinfunction "8_8") (pintype "input"))
      (node (ref "Q20") (pin "2") (pinfunction "S_2") (pintype "unspecified"))
      (node (ref "R47") (pin "1") (pinfunction "1_1") (pintype "input"))
    )
    (net (code "8") (name "Net-(D2-A)") (class "Default")
      (node (ref "D2") (pin "2") (pinfunction "A_2") (pintype "unspecified"))
      (node (ref "K3") (pin "4") (pinfunction "4_4") (pintype "unspecified"))
      (node (ref "Q3") (pin "3") (pinfunction "C_3") (pintype "unspecified"))
    )
    (net (code "9") (name "Net-(D10-A)") (class "Default")
      (node (ref "CN1") (pin "2") (pinfunction "2_2") (pintype "unspecified"))
      (node (ref "D10") (pin "2") (pinfunction "A_2") (pintype "unspecified"))
      (node (ref "Q19") (pin "2") (pinfunction "D_2") (pintype "unspecified"))
    )
    (net (code "10") (name "Net-(K3-Pad1)") (class "Default")
      (node (ref "K3") (pin "1") (pinfunction "1_1") (pintype "unspecified"))
      (node (ref "P2") (pin "3") (pinfunction "3_3") (pintype "unspecified"))
    )
    (net (code "11") (name "Net-(K3-Pad2)") (class "Default")
      (node (ref "K3") (pin "2") (pinfunction "2_2") (pintype "unspecified"))
      (node (ref "P2") (pin "1") (pinfunction "1_1") (pintype "unspecified"))
    )
    (net (code "12") (name "Net-(K3-Pad5)") (class "Default")
      (node (ref "K3") (pin "5") (pinfunction "5_5") (pintype "unspecified"))
      (node (ref "P2") (pin "2") (pinfunction "2_2") (pintype "unspecified"))
    )
    (net (code "13") (name "Net-(LED5-A)") (class "Default")
      (node (ref "LED5") (pin "1") (pinfunction "A_1") (pintype "input"))
      (node (ref "U20") (pin "2") (pinfunction "2_2") (pintype "unspecified"))
    )
    (net (code "14") (name "Net-(LED5-C)") (class "Default")
      (node (ref "LED5") (pin "2") (pinfunction "C_2") (pintype "input"))
      (node (ref "Q7") (pin "3") (pinfunction "D_3") (pintype "unspecified"))
      (node (ref "R8") (pin "1") (pinfunction "1_1") (pintype "input"))
    )
    (net (code "15") (name "Net-(LED10-A)") (class "Default")
      (node (ref "LED10") (pin "1") (pinfunction "A_1") (pintype "input"))
      (node (ref "U18") (pin "2") (pinfunction "2_2") (pintype "unspecified"))
    )
    (net (code "16") (name "Net-(LED10-C)") (class "Default")
      (node (ref "LED10") (pin "2") (pinfunction "C_2") (pintype "input"))
      (node (ref "Q20") (pin "3") (pinfunction "D_3") (pintype "unspecified"))
      (node (ref "R48") (pin "1") (pinfunction "1_1") (pintype "input"))
    )
    (net (code "17") (name "Net-(Q3-B)") (class "Default")
      (node (ref "Q3") (pin "1") (pinfunction "B_1") (pintype "unspecified"))
      (node (ref "R6") (pin "2") (pinfunction "2_2") (pintype "input"))
    )
    (net (code "18") (name "Net-(Q19-G)") (class "Default")
      (node (ref "Q19") (pin "1") (pinfunction "G_1") (pintype "unspecified"))
      (node (ref "R45") (pin "2") (pinfunction "2_2") (pintype "input"))
      (node (ref "R49") (pin "2") (pinfunction "2_2") (pintype "input"))
    )
    (net (code "19") (name "Net-(R5-Pad1)") (class "Default")
      (node (ref "R5") (pin "1") (pinfunction "1_1") (pintype "input"))
      (node (ref "U20") (pin "1") (pinfunction "1_1") (pintype "unspecified"))
    )
    (net (code "20") (name "Net-(R6-Pad1)") (class "Default")
      (node (ref "R6") (pin "1") (pinfunction "1_1") (pintype "input"))
      (node (ref "U20") (pin "3") (pinfunction "3_3") (pintype "unspecified"))
    )
    (net (code "21") (name "Net-(R36-Pad1)") (class "Default")
      (node (ref "R36") (pin "1") (pinfunction "1_1") (pintype "input"))
      (node (ref "U18") (pin "1") (pinfunction "1_1") (pintype "unspecified"))
    )
    (net (code "22") (name "Net-(R45-Pad1)") (class "Default")
      (node (ref "R45") (pin "1") (pinfunction "1_1") (pintype "input"))
      (node (ref "U18") (pin "3") (pinfunction "3_3") (pintype "unspecified"))
    )
    (net (code "23") (name "RST") (class "Default")
      (node (ref "H1") (pin "5") (pinfunction "5_5") (pintype "input"))
      (node (ref "H2") (pin "5") (pinfunction "5_5") (pintype "input"))
      (node (ref "H3") (pin "5") (pinfunction "5_5") (pintype "input"))
      (node (ref "R12") (pin "2") (pinfunction "2_2") (pintype "input"))
      (node (ref "R2") (pin "2") (pinfunction "2_2") (pintype "input"))
      (node (ref "R9") (pin "2") (pinfunction "2_2") (pintype "input"))
      (node (ref "SW1") (pin "1") (pinfunction "A_1") (pintype "unspecified"))
      (node (ref "SW2") (pin "1") (pinfunction "A_1") (pintype "unspecified"))
      (node (ref "SW3") (pin "1") (pinfunction "A_1") (pintype "unspecified"))
    )
    (net (code "24") (name "VCC") (class "Default")
      (node (ref "C10") (pin "2") (pinfunction "2_2") (pintype "input"))
      (node (ref "C13") (pin "2") (pinfunction "2_2") (pintype "input"))
      (node (ref "C15") (pin "2") (pinfunction "2_2") (pintype "input"))
      (node (ref "C3") (pin "2") (pinfunction "2_2") (pintype "input"))
      (node (ref "C5") (pin "2") (pinfunction "2_2") (pintype "input"))
      (node (ref "C7") (pin "2") (pinfunction "2_2") (pintype "input"))
      (node (ref "H1") (pin "7") (pinfunction "7_7") (pintype "input"))
      (node (ref "H2") (pin "7") (pinfunction "7_7") (pintype "input"))
      (node (ref "H3") (pin "7") (pinfunction "7_7") (pintype "input"))
      (node (ref "Q20") (pin "1") (pinfunction "G_1") (pintype "unspecified"))
      (node (ref "Q7") (pin "1") (pinfunction "G_1") (pintype "unspecified"))
      (node (ref "R1") (pin "1") (pinfunction "1_1") (pintype "input"))
      (node (ref "R10") (pin "1") (pinfunction "1_1") (pintype "input"))
      (node (ref "R11") (pin "1") (pinfunction "1_1") (pintype "input"))
      (node (ref "R12") (pin "1") (pinfunction "1_1") (pintype "input"))
      (node (ref "R13") (pin "1") (pinfunction "1_1") (pintype "input"))
      (node (ref "R14") (pin "2") (pinfunction "2_2") (pintype "input"))
      (node (ref "R15") (pin "2") (pinfunction "2_2") (pintype "input"))
      (node (ref "R17") (pin "2") (pinfunction "2_2") (pintype "input"))
      (node (ref "R2") (pin "1") (pinfunction "1_1") (pintype "input"))
      (node (ref "R3") (pin "1") (pinfunction "1_1") (pintype "input"))
      (node (ref "R4") (pin "1") (pinfunction "1_1") (pintype "input"))
      (node (ref "R47") (pin "2") (pinfunction "2_2") (pintype "input"))
      (node (ref "R7") (pin "2") (pinfunction "2_2") (pintype "input"))
      (node (ref "R9") (pin "1") (pinfunction "1_1") (pintype "input"))
      (node (ref "U1") (pin "2") (pinfunction "Vout_2") (pintype "unspecified"))
      (node (ref "U3") (pin "2") (pinfunction "Vout_2") (pintype "unspecified"))
      (node (ref "U8") (pin "2") (pinfunction "Vout_2") (pintype "unspecified"))
    )
    (net (code "25") (name "relay 1") (class "Default")
      (node (ref "H1") (pin "8") (pinfunction "8_8") (pintype "input"))
      (node (ref "Q7") (pin "2") (pinfunction "S_2") (pintype "unspecified"))
      (node (ref "R7") (pin "1") (pinfunction "1_1") (pintype "input"))
    )
    (net (code "26") (name "switch 1") (class "Default")
      (node (ref "CN2") (pin "1") (pinfunction "1_1") (pintype "unspecified"))
      (node (ref "CN3") (pin "1") (pinfunction "1_1") (pintype "unspecified"))
      (node (ref "CN9") (pin "1") (pinfunction "1_1") (pintype "unspecified"))
      (node (ref "H1") (pin "1") (pinfunction "1_1") (pintype "input"))
      (node (ref "H2") (pin "1") (pinfunction "1_1") (pintype "input"))
      (node (ref "H3") (pin "1") (pinfunction "1_1") (pintype "input"))
      (node (ref "R14") (pin "1") (pinfunction "1_1") (pintype "input"))
      (node (ref "R15") (pin "1") (pinfunction "1_1") (pintype "input"))
      (node (ref "R17") (pin "1") (pinfunction "1_1") (pintype "input"))
    )
    (net (code "27") (name "unconnected-(K3-Pad6)") (class "Default")
      (node (ref "K3") (pin "6") (pinfunction "6_6") (pintype "unspecified+no_connect"))
    )
    (net (code "28") (name "unconnected-(SW1-B-Pad2)") (class "Default")
      (node (ref "SW1") (pin "2") (pinfunction "B_2") (pintype "unspecified+no_connect"))
    )
    (net (code "29") (name "unconnected-(SW1-D-Pad4)") (class "Default")
      (node (ref "SW1") (pin "4") (pinfunction "D_4") (pintype "unspecified+no_connect"))
    )
    (net (code "30") (name "unconnected-(SW2-B-Pad2)") (class "Default")
      (node (ref "SW2") (pin "2") (pinfunction "B_2") (pintype "unspecified+no_connect"))
    )
    (net (code "31") (name "unconnected-(SW2-D-Pad4)") (class "Default")
      (node (ref "SW2") (pin "4") (pinfunction "D_4") (pintype "unspecified+no_connect"))
    )
    (net (code "32") (name "unconnected-(SW3-B-Pad2)") (class "Default")
      (node (ref "SW3") (pin "2") (pinfunction "B_2") (pintype "unspecified+no_connect"))
    )
    (net (code "33") (name "unconnected-(SW3-D-Pad4)") (class "Default")
      (node (ref "SW3") (pin "4") (pinfunction "D_4") (pintype "unspecified+no_connect"))
    )
    (net (code "34") (name "unconnected-(U1-Vout-Pad4)") (class "Default")
      (node (ref "U1") (pin "4") (pinfunction "Vout_4") (pintype "unspecified+no_connect"))
    )
    (net (code "35") (name "unconnected-(U3-Vout-Pad4)") (class "Default")
      (node (ref "U3") (pin "4") (pinfunction "Vout_4") (pintype "unspecified+no_connect"))
    )
    (net (code "36") (name "unconnected-(U8-Vout-Pad4)") (class "Default")
      (node (ref "U8") (pin "4") (pinfunction "Vout_4") (pintype "unspecified+no_connect"))
    )
  )
)
